# okkb-pic-badge.net
KiCad netlist of a schematic drawn in EAGLE
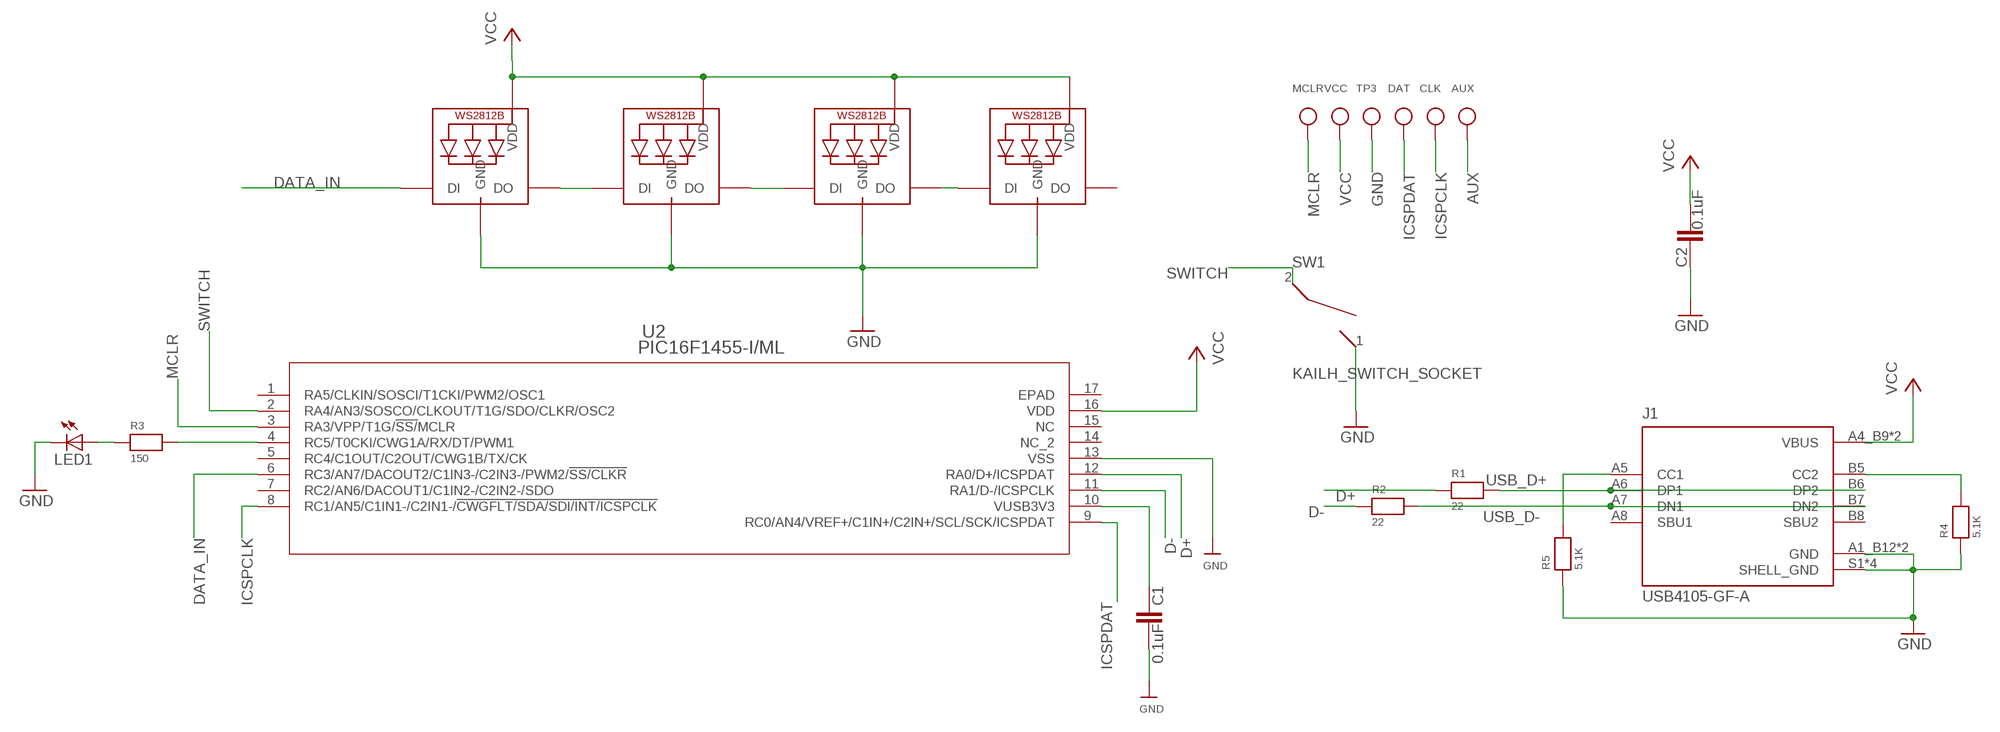
[diagram p0: schematic, sheet 1]

(export (version "E")
  (design (tool "Eeschema 10.0.6"))
  (components
    (comp (ref "AUX")
      (value "TESTPOINTROUND1MM")
      (footprint "eagle-import:TESTPOINT_ROUND_1MM")
      (libsource (lib "eagle-import") (part "TESTPOINTROUND1MM"))
    )
    (comp (ref "C1")
      (value "0.1uF")
      (footprint "eagle-import:C0805")
      (libsource (lib "eagle-import") (part "CAPACITOR-C0805"))
    )
    (comp (ref "C2")
      (value "0.1uF")
      (footprint "eagle-import:C0805")
      (libsource (lib "eagle-import") (part "CAPACITOR-C0805"))
    )
    (comp (ref "CLK")
      (value "TESTPOINTROUND1MM")
      (footprint "eagle-import:TESTPOINT_ROUND_1MM")
      (libsource (lib "eagle-import") (part "TESTPOINTROUND1MM"))
    )
    (comp (ref "DAT")
      (value "TESTPOINTROUND1MM")
      (footprint "eagle-import:TESTPOINT_ROUND_1MM")
      (libsource (lib "eagle-import") (part "TESTPOINTROUND1MM"))
    )
    (comp (ref "J1")
      (value "USB4105-GF-A")
      (footprint "eagle-import:GCT_USB4105-GF-A")
      (fields (field (name "MF") "GCT"))
      (libsource (lib "eagle-import") (part "USB4105-GF-A"))
    )
    (comp (ref "LED1")
      (value "LEDCHIPLED_1206")
      (footprint "eagle-import:CHIPLED_1206")
      (libsource (lib "eagle-import") (part "LEDCHIPLED_1206"))
    )
    (comp (ref "LED2")
      (value "WS2812B3535")
      (footprint "eagle-import:LED3535")
      (libsource (lib "eagle-import") (part "WS2812B3535"))
    )
    (comp (ref "LED3")
      (value "WS2812B3535")
      (footprint "eagle-import:LED3535")
      (libsource (lib "eagle-import") (part "WS2812B3535"))
    )
    (comp (ref "LED4")
      (value "WS2812B3535")
      (footprint "eagle-import:LED3535")
      (libsource (lib "eagle-import") (part "WS2812B3535"))
    )
    (comp (ref "LED5")
      (value "WS2812B3535")
      (footprint "eagle-import:LED3535")
      (libsource (lib "eagle-import") (part "WS2812B3535"))
    )
    (comp (ref "MCLR")
      (value "TESTPOINTROUND1MM")
      (footprint "eagle-import:TESTPOINT_ROUND_1MM")
      (libsource (lib "eagle-import") (part "TESTPOINTROUND1MM"))
    )
    (comp (ref "R1")
      (value "22")
      (footprint "eagle-import:0805")
      (libsource (lib "eagle-import") (part "RESISTOR0805"))
    )
    (comp (ref "R2")
      (value "22")
      (footprint "eagle-import:0805")
      (libsource (lib "eagle-import") (part "RESISTOR0805"))
    )
    (comp (ref "R3")
      (value "150")
      (footprint "eagle-import:_0805")
      (libsource (lib "eagle-import") (part "RESISTOR_0805"))
    )
    (comp (ref "R4")
      (value "5.1K")
      (footprint "eagle-import:0805")
      (libsource (lib "eagle-import") (part "RESISTOR0805"))
    )
    (comp (ref "R5")
      (value "5.1K")
      (footprint "eagle-import:0805")
      (libsource (lib "eagle-import") (part "RESISTOR0805"))
    )
    (comp (ref "SW1")
      (value "KAILH_SWITCH_SOCKET")
      (footprint "eagle-import:SWITCH_SOCKET")
      (libsource (lib "eagle-import") (part "KAILH_SWITCH_SOCKET"))
    )
    (comp (ref "TP3")
      (value "TESTPOINTROUND1MM")
      (footprint "eagle-import:TESTPOINT_ROUND_1MM")
      (libsource (lib "eagle-import") (part "TESTPOINTROUND1MM"))
    )
    (comp (ref "U2")
      (value "PIC16F1455-I/ML")
      (footprint "eagle-import:QFN16_4X4MC")
      (fields (field (name "MANUFACTURER_PART_NUMBER") "pic16f1455iml"))
      (libsource (lib "eagle-import") (part "PIC16F1455-I/ML"))
    )
    (comp (ref "VCC")
      (value "TESTPOINTROUND1MM")
      (footprint "eagle-import:TESTPOINT_ROUND_1MM")
      (libsource (lib "eagle-import") (part "TESTPOINTROUND1MM"))
    )
  )
  (nets
    (net (code "1") (name "/AUX") (class "Default")
      (node (ref "AUX") (pin "P$1") (pinfunction "P$1_P$1") (pintype "bidirectional"))
    )
    (net (code "2") (name "/D+") (class "Default")
      (node (ref "R1") (pin "1") (pinfunction "1_1") (pintype "passive"))
      (node (ref "U2") (pin "12") (pinfunction "RA0/D+/ICSPDAT_12") (pintype "bidirectional"))
    )
    (net (code "3") (name "/D-") (class "Default")
      (node (ref "R2") (pin "1") (pinfunction "1_1") (pintype "passive"))
      (node (ref "U2") (pin "11") (pinfunction "RA1/D-/ICSPCLK_11") (pintype "bidirectional"))
    )
    (net (code "4") (name "/DATA_IN") (class "Default")
      (node (ref "LED2") (pin "1") (pinfunction "DI_1") (pintype "input"))
      (node (ref "U2") (pin "6") (pinfunction "RC3/AN7/DACOUT2/C1IN3-/C2IN3-/PWM2/~{SS/CLKR}_6") (pintype "bidirectional"))
    )
    (net (code "5") (name "/ICSPCLK") (class "Default")
      (node (ref "CLK") (pin "P$1") (pinfunction "P$1_P$1") (pintype "bidirectional"))
      (node (ref "U2") (pin "8") (pinfunction "RC1/AN5/C1IN1-/C2IN1-/~{CWGFLT/SDA/SDI/INT/ICSPCLK}_8") (pintype "bidirectional"))
    )
    (net (code "6") (name "/ICSPDAT") (class "Default")
      (node (ref "DAT") (pin "P$1") (pinfunction "P$1_P$1") (pintype "bidirectional"))
      (node (ref "U2") (pin "9") (pinfunction "RC0/AN4/VREF+/C1IN+/C2IN+/SCL/SCK/ICSPDAT_9") (pintype "bidirectional"))
    )
    (net (code "7") (name "/MCLR") (class "Default")
      (node (ref "MCLR") (pin "P$1") (pinfunction "P$1_P$1") (pintype "bidirectional"))
      (node (ref "U2") (pin "3") (pinfunction "RA3/VPP/T1G/~{SS/}MCLR_3") (pintype "bidirectional"))
    )
    (net (code "8") (name "/SWITCH") (class "Default")
      (node (ref "SW1") (pin "2") (pinfunction "1_2") (pintype "passive"))
      (node (ref "U2") (pin "2") (pinfunction "RA4/AN3/SOSCO/CLKOUT/T1G/SDO/CLKR/OSC2_2") (pintype "bidirectional"))
    )
    (net (code "9") (name "/USB_D+") (class "Default")
      (node (ref "J1") (pin "A6") (pinfunction "DP1_A6") (pintype "bidirectional"))
      (node (ref "J1") (pin "B6") (pinfunction "DP2_B6") (pintype "bidirectional"))
      (node (ref "R1") (pin "2") (pinfunction "2_2") (pintype "passive"))
    )
    (net (code "10") (name "/USB_D-") (class "Default")
      (node (ref "J1") (pin "A7") (pinfunction "DN1_A7") (pintype "bidirectional"))
      (node (ref "J1") (pin "B7") (pinfunction "DN2_B7") (pintype "bidirectional"))
      (node (ref "R2") (pin "2") (pinfunction "2_2") (pintype "passive"))
    )
    (net (code "11") (name "GND") (class "Default")
      (node (ref "C1") (pin "2") (pinfunction "2_2") (pintype "passive"))
      (node (ref "C2") (pin "1") (pinfunction "1_1") (pintype "passive"))
      (node (ref "J1") (pin "A1_B12") (pinfunction "GND_A1_B12") (pintype "power_in"))
      (node (ref "J1") (pin "B1_A12") (pinfunction "GND_B1_A12") (pintype "power_in"))
      (node (ref "J1") (pin "S1") (pinfunction "SHELL_GND_S1") (pintype "power_in"))
      (node (ref "J1") (pin "S2") (pinfunction "SHELL_GND_S2") (pintype "power_in"))
      (node (ref "J1") (pin "S3") (pinfunction "SHELL_GND_S3") (pintype "power_in"))
      (node (ref "J1") (pin "S4") (pinfunction "SHELL_GND_S4") (pintype "power_in"))
      (node (ref "LED1") (pin "C") (pinfunction "C_C") (pintype "passive"))
      (node (ref "LED2") (pin "4") (pinfunction "GND_4") (pintype "power_in"))
      (node (ref "LED3") (pin "4") (pinfunction "GND_4") (pintype "power_in"))
      (node (ref "LED4") (pin "4") (pinfunction "GND_4") (pintype "power_in"))
      (node (ref "LED5") (pin "4") (pinfunction "GND_4") (pintype "power_in"))
      (node (ref "R4") (pin "1") (pinfunction "1_1") (pintype "passive"))
      (node (ref "R5") (pin "1") (pinfunction "1_1") (pintype "passive"))
      (node (ref "SW1") (pin "1") (pinfunction "2_1") (pintype "passive"))
      (node (ref "TP3") (pin "P$1") (pinfunction "P$1_P$1") (pintype "bidirectional"))
      (node (ref "U2") (pin "13") (pinfunction "VSS_13") (pintype "power_in"))
    )
    (net (code "12") (name "Net-(J1-CC1)") (class "Default")
      (node (ref "J1") (pin "A5") (pinfunction "CC1_A5") (pintype "bidirectional"))
      (node (ref "R5") (pin "2") (pinfunction "2_2") (pintype "passive"))
    )
    (net (code "13") (name "Net-(J1-CC2)") (class "Default")
      (node (ref "J1") (pin "B5") (pinfunction "CC2_B5") (pintype "bidirectional"))
      (node (ref "R4") (pin "2") (pinfunction "2_2") (pintype "passive"))
    )
    (net (code "14") (name "Net-(LED1-PadA)") (class "Default")
      (node (ref "LED1") (pin "A") (pinfunction "A_A") (pintype "passive"))
      (node (ref "R3") (pin "1") (pinfunction "1_1") (pintype "passive"))
    )
    (net (code "15") (name "Net-(LED2-DO)") (class "Default")
      (node (ref "LED2") (pin "3") (pinfunction "DO_3") (pintype "output"))
      (node (ref "LED3") (pin "1") (pinfunction "DI_1") (pintype "input"))
    )
    (net (code "16") (name "Net-(LED3-DO)") (class "Default")
      (node (ref "LED3") (pin "3") (pinfunction "DO_3") (pintype "output"))
      (node (ref "LED4") (pin "1") (pinfunction "DI_1") (pintype "input"))
    )
    (net (code "17") (name "Net-(LED4-DO)") (class "Default")
      (node (ref "LED4") (pin "3") (pinfunction "DO_3") (pintype "output"))
      (node (ref "LED5") (pin "1") (pinfunction "DI_1") (pintype "input"))
    )
    (net (code "18") (name "Net-(U2-RC5{slash}T0CKI{slash}CWG1A{slash}RX{slash}DT{slash}PWM1)") (class "Default")
      (node (ref "R3") (pin "2") (pinfunction "2_2") (pintype "passive"))
      (node (ref "U2") (pin "4") (pinfunction "RC5/T0CKI/CWG1A/RX/DT/PWM1_4") (pintype "bidirectional"))
    )
    (net (code "19") (name "Net-(U2-VUSB3V3)") (class "Default")
      (node (ref "C1") (pin "1") (pinfunction "1_1") (pintype "passive"))
      (node (ref "U2") (pin "10") (pinfunction "VUSB3V3_10") (pintype "power_in"))
    )
    (net (code "20") (name "VCC") (class "Default")
      (node (ref "C2") (pin "2") (pinfunction "2_2") (pintype "passive"))
      (node (ref "J1") (pin "A4_B9") (pinfunction "VBUS_A4_B9") (pintype "power_in"))
      (node (ref "J1") (pin "B4_A9") (pinfunction "VBUS_B4_A9") (pintype "power_in"))
      (node (ref "LED2") (pin "2") (pinfunction "VDD_2") (pintype "power_in"))
      (node (ref "LED3") (pin "2") (pinfunction "VDD_2") (pintype "power_in"))
      (node (ref "LED4") (pin "2") (pinfunction "VDD_2") (pintype "power_in"))
      (node (ref "LED5") (pin "2") (pinfunction "VDD_2") (pintype "power_in"))
      (node (ref "U2") (pin "16") (pinfunction "VDD_16") (pintype "power_in"))
      (node (ref "VCC") (pin "P$1") (pinfunction "P$1_P$1") (pintype "bidirectional"))
    )
    (net (code "21") (name "unconnected-(J1-SBU1-PadA8)") (class "Default")
      (node (ref "J1") (pin "A8") (pinfunction "SBU1_A8") (pintype "bidirectional"))
    )
    (net (code "22") (name "unconnected-(J1-SBU2-PadB8)") (class "Default")
      (node (ref "J1") (pin "B8") (pinfunction "SBU2_B8") (pintype "bidirectional"))
    )
    (net (code "23") (name "unconnected-(LED5-DO-Pad3)") (class "Default")
      (node (ref "LED5") (pin "3") (pinfunction "DO_3") (pintype "output"))
    )
    (net (code "24") (name "unconnected-(U2-EPAD-Pad17)") (class "Default")
      (node (ref "U2") (pin "17") (pinfunction "EPAD_17") (pintype "passive"))
    )
    (net (code "25") (name "unconnected-(U2-NC-Pad15)") (class "Default")
      (node (ref "U2") (pin "15") (pinfunction "NC_15") (pintype "no_connect"))
    )
    (net (code "26") (name "unconnected-(U2-NC_2-Pad14)") (class "Default")
      (node (ref "U2") (pin "14") (pinfunction "NC_2_14") (pintype "no_connect"))
    )
    (net (code "27") (name "unconnected-(U2-RA5{slash}CLKIN{slash}SOSCI{slash}T1CKI{slash}PWM2{slash}OSC1-Pad1)") (class "Default")
      (node (ref "U2") (pin "1") (pinfunction "RA5/CLKIN/SOSCI/T1CKI/PWM2/OSC1_1") (pintype "bidirectional"))
    )
    (net (code "28") (name "unconnected-(U2-RC2{slash}AN6{slash}DACOUT1{slash}C1IN2-{slash}C2IN2-{slash}SDO-Pad7)") (class "Default")
      (node (ref "U2") (pin "7") (pinfunction "RC2/AN6/DACOUT1/C1IN2-/C2IN2-/SDO_7") (pintype "bidirectional"))
    )
    (net (code "29") (name "unconnected-(U2-RC4{slash}C1OUT{slash}C2OUT{slash}CWG1B{slash}TX{slash}CK-Pad5)") (class "Default")
      (node (ref "U2") (pin "5") (pinfunction "RC4/C1OUT/C2OUT/CWG1B/TX/CK_5") (pintype "bidirectional"))
    )
  )
)
